# Super_IO.net
KiCad netlist of a schematic drawn in Altium Designer
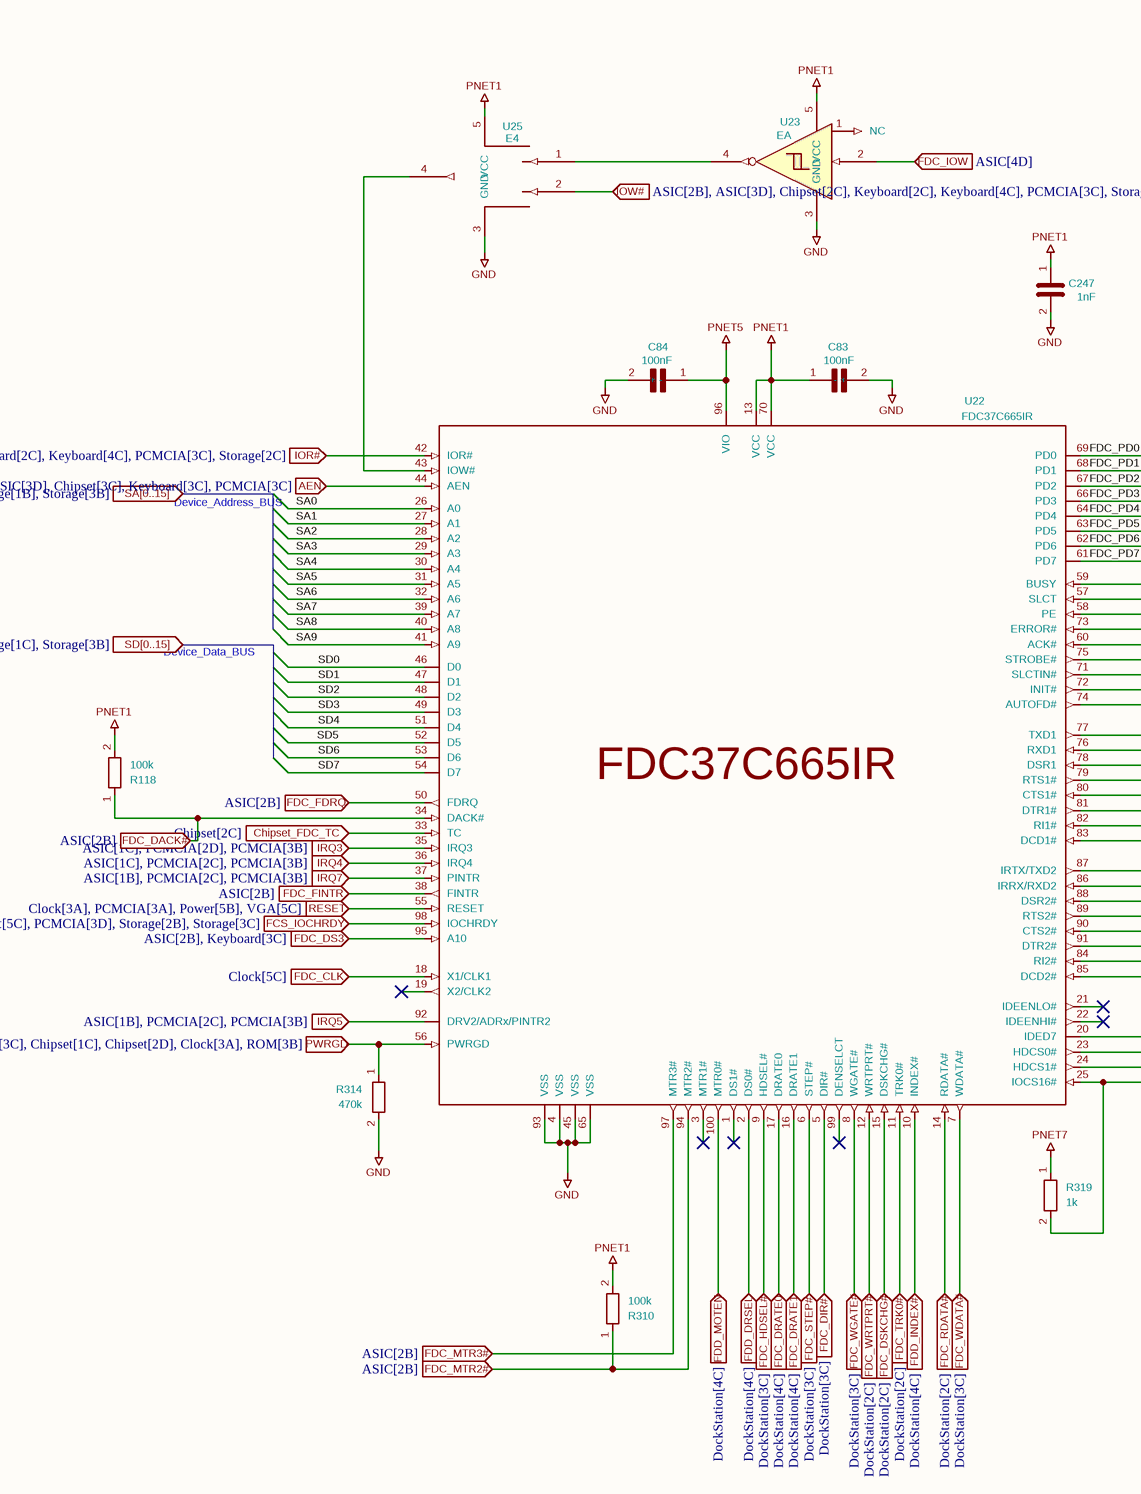
[diagram p0: Super_IO.SchDoc, left]
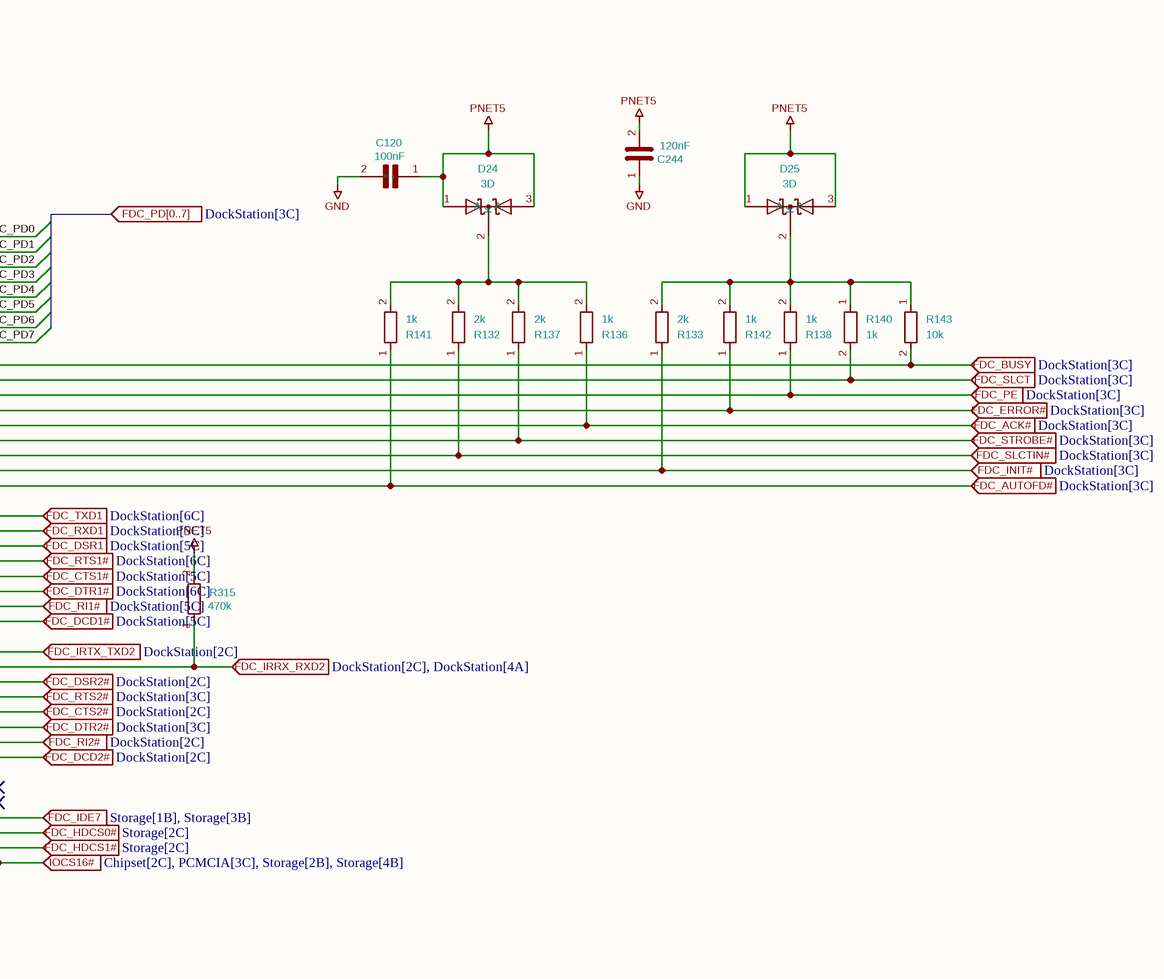
[diagram p1: Super_IO.SchDoc, right]

(export (version "E")
  (design (tool "Eeschema 10.0.6"))
  (components
    (comp (ref "C83") (value "100nF") (footprint "C_0402_1005Metric") (libsource (lib "") (part "C_1")))
    (comp (ref "C84")
      (value "100nF")
      (footprint "C_0402_1005Metric")
      (libsource (lib "PCM_Elektuur") (part "C"))
    )
    (comp (ref "C120")
      (value "100nF")
      (footprint "C_0402_1005Metric")
      (libsource (lib "PCM_Elektuur") (part "C"))
    )
    (comp (ref "C244") (value "120nF") (footprint "C_0402_1005Metric") (libsource (lib "Device") (part "C")))
    (comp (ref "C247") (value "1nF") (footprint "C_0402_1005Metric") (libsource (lib "Device") (part "C")))
    (comp (ref "D24")
      (value "3D")
      (footprint "3D")
      (libsource (lib "Device") (part "D_Schottky_Dual_CommonCathode_AKA"))
    )
    (comp (ref "D25")
      (value "3D")
      (footprint "3D")
      (libsource (lib "Device") (part "D_Schottky_Dual_CommonCathode_AKA"))
    )
    (comp (ref "R118") (value "100k") (footprint "R_0402_1005Metric") (libsource (lib "Device") (part "R")))
    (comp (ref "R132") (value "2k") (footprint "R_0402_1005Metric") (libsource (lib "Device") (part "R")))
    (comp (ref "R133") (value "2k") (footprint "R_0402_1005Metric") (libsource (lib "Device") (part "R")))
    (comp (ref "R136") (value "1k") (footprint "R_0402_1005Metric") (libsource (lib "Device") (part "R")))
    (comp (ref "R137") (value "2k") (footprint "R_0402_1005Metric") (libsource (lib "Device") (part "R")))
    (comp (ref "R138") (value "1k") (footprint "R_0402_1005Metric") (libsource (lib "Device") (part "R")))
    (comp (ref "R140") (value "1k") (footprint "R_0402_1005Metric") (libsource (lib "") (part "R_1")))
    (comp (ref "R141") (value "1k") (footprint "R_0402_1005Metric") (libsource (lib "Device") (part "R")))
    (comp (ref "R142") (value "1k") (footprint "R_0402_1005Metric") (libsource (lib "Device") (part "R")))
    (comp (ref "R143") (value "10k") (footprint "R_0402_1005Metric") (libsource (lib "") (part "R_1")))
    (comp (ref "R310") (value "100k") (footprint "R_0402_1005Metric") (libsource (lib "Device") (part "R")))
    (comp (ref "R314") (value "470k") (footprint "R_0402_1005Metric") (libsource (lib "") (part "R_2")))
    (comp (ref "R315") (value "470k") (footprint "R_0402_1005Metric") (libsource (lib "Device") (part "R")))
    (comp (ref "R319") (value "1k") (footprint "R_0402_1005Metric") (libsource (lib "") (part "R_1")))
    (comp (ref "U22") (value "FDC37C665IR") (footprint "FDC") (libsource (lib "PC110") (part "FDC37C665IR")))
    (comp (ref "U23") (value "EA") (footprint "SOT-353") (libsource (lib "74xGxx") (part "74AHC1G14")))
    (comp (ref "U25") (value "E4") (footprint "SOT-353") (libsource (lib "74xGxx") (part "74AHC1G32")))
  )
  (nets
    (net (code "15") (name "/AEN") (class "Default")
      (node (ref "U22") (pin "44") (pinfunction "AEN_44") (pintype "input"))
    )
    (net (code "16") (name "/Chipset_FDC_TC") (class "Default")
      (node (ref "U22") (pin "33") (pinfunction "TC_33") (pintype "input"))
    )
    (net (code "17") (name "/FCS_IOCHRDY") (class "Default")
      (node (ref "U22") (pin "98") (pinfunction "IOCHRDY_98") (pintype "input"))
    )
    (net (code "18") (name "/FDC_ACK#") (class "Default")
      (node (ref "R136") (pin "1") (pinfunction "1_1") (pintype "passive"))
      (node (ref "U22") (pin "60") (pinfunction "ACK#_60") (pintype "input"))
    )
    (net (code "19") (name "/FDC_AUTOFD#") (class "Default")
      (node (ref "R141") (pin "1") (pinfunction "1_1") (pintype "passive"))
      (node (ref "U22") (pin "74") (pinfunction "AUTOFD#_74") (pintype "output"))
    )
    (net (code "20") (name "/FDC_BUSY") (class "Default")
      (node (ref "R143") (pin "2") (pinfunction "2_2") (pintype "passive"))
      (node (ref "U22") (pin "59") (pinfunction "BUSY_59") (pintype "input"))
    )
    (net (code "21") (name "/FDC_CLK") (class "Default")
      (node (ref "U22") (pin "18") (pinfunction "X1/CLK1_18") (pintype "input"))
    )
    (net (code "22") (name "/FDC_CTS1#") (class "Default")
      (node (ref "U22") (pin "80") (pinfunction "CTS1#_80") (pintype "input"))
    )
    (net (code "23") (name "/FDC_CTS2#") (class "Default")
      (node (ref "U22") (pin "90") (pinfunction "CTS2#_90") (pintype "input"))
    )
    (net (code "24") (name "/FDC_DACK#") (class "Default")
      (node (ref "R118") (pin "1") (pinfunction "1_1") (pintype "passive"))
      (node (ref "U22") (pin "34") (pinfunction "DACK#_34") (pintype "input"))
    )
    (net (code "25") (name "/FDC_DCD1#") (class "Default")
      (node (ref "U22") (pin "83") (pinfunction "DCD1#_83") (pintype "input"))
    )
    (net (code "26") (name "/FDC_DCD2#") (class "Default")
      (node (ref "U22") (pin "85") (pinfunction "DCD2#_85") (pintype "input"))
    )
    (net (code "27") (name "/FDC_DIR#") (class "Default")
      (node (ref "U22") (pin "5") (pinfunction "DIR#_5") (pintype "output"))
    )
    (net (code "28") (name "/FDC_DRATE0") (class "Default")
      (node (ref "U22") (pin "17") (pinfunction "DRATE0_17") (pintype "output"))
    )
    (net (code "29") (name "/FDC_DRATE1") (class "Default")
      (node (ref "U22") (pin "16") (pinfunction "DRATE1_16") (pintype "output"))
    )
    (net (code "30") (name "/FDC_DS3") (class "Default")
      (node (ref "U22") (pin "95") (pinfunction "A10_95") (pintype "input"))
    )
    (net (code "31") (name "/FDC_DSKCHG#") (class "Default")
      (node (ref "U22") (pin "15") (pinfunction "DSKCHG#_15") (pintype "input"))
    )
    (net (code "32") (name "/FDC_DSR1") (class "Default")
      (node (ref "U22") (pin "78") (pinfunction "DSR1_78") (pintype "input"))
    )
    (net (code "33") (name "/FDC_DSR2#") (class "Default")
      (node (ref "U22") (pin "88") (pinfunction "DSR2#_88") (pintype "input"))
    )
    (net (code "34") (name "/FDC_DTR1#") (class "Default")
      (node (ref "U22") (pin "81") (pinfunction "DTR1#_81") (pintype "output"))
    )
    (net (code "35") (name "/FDC_DTR2#") (class "Default")
      (node (ref "U22") (pin "91") (pinfunction "DTR2#_91") (pintype "output"))
    )
    (net (code "36") (name "/FDC_ERROR#") (class "Default")
      (node (ref "R142") (pin "1") (pinfunction "1_1") (pintype "passive"))
      (node (ref "U22") (pin "73") (pinfunction "ERROR#_73") (pintype "input"))
    )
    (net (code "37") (name "/FDC_FDRQ") (class "Default")
      (node (ref "U22") (pin "50") (pinfunction "FDRQ_50") (pintype "output"))
    )
    (net (code "38") (name "/FDC_FINTR") (class "Default")
      (node (ref "U22") (pin "38") (pinfunction "FINTR_38") (pintype "output"))
    )
    (net (code "39") (name "/FDC_HDCS0#") (class "Default")
      (node (ref "U22") (pin "23") (pinfunction "HDCS0#_23") (pintype "output"))
    )
    (net (code "40") (name "/FDC_HDCS1#") (class "Default")
      (node (ref "U22") (pin "24") (pinfunction "HDCS1#_24") (pintype "output"))
    )
    (net (code "41") (name "/FDC_HDSEL#") (class "Default")
      (node (ref "U22") (pin "9") (pinfunction "HDSEL#_9") (pintype "output"))
    )
    (net (code "42") (name "/FDC_IDE7") (class "Default")
      (node (ref "U22") (pin "20") (pinfunction "IDED7_20") (pintype "bidirectional"))
    )
    (net (code "43") (name "/FDC_INIT#") (class "Default")
      (node (ref "R133") (pin "1") (pinfunction "1_1") (pintype "passive"))
      (node (ref "U22") (pin "72") (pinfunction "INIT#_72") (pintype "output"))
    )
    (net (code "44") (name "/FDC_IOW") (class "Default")
      (node (ref "U23") (pin "2") (pinfunction "2_2") (pintype "input"))
    )
    (net (code "45") (name "/FDC_IRRX_RXD2") (class "Default")
      (node (ref "R315") (pin "1") (pinfunction "1_1") (pintype "passive"))
      (node (ref "U22") (pin "86") (pinfunction "IRRX/RXD2_86") (pintype "input"))
    )
    (net (code "46") (name "/FDC_IRTX_TXD2") (class "Default")
      (node (ref "U22") (pin "87") (pinfunction "IRTX/TXD2_87") (pintype "output"))
    )
    (net (code "47") (name "/FDC_MTR2#") (class "Default")
      (node (ref "R310") (pin "1") (pinfunction "1_1") (pintype "passive"))
      (node (ref "U22") (pin "94") (pinfunction "MTR2#_94") (pintype "output"))
    )
    (net (code "48") (name "/FDC_MTR3#") (class "Default")
      (node (ref "U22") (pin "97") (pinfunction "MTR3#_97") (pintype "output"))
    )
    (net (code "49") (name "/FDC_PD0") (class "Default")
      (node (ref "U22") (pin "69") (pinfunction "PD0_69") (pintype "bidirectional"))
    )
    (net (code "50") (name "/FDC_PD1") (class "Default")
      (node (ref "U22") (pin "68") (pinfunction "PD1_68") (pintype "bidirectional"))
    )
    (net (code "51") (name "/FDC_PD2") (class "Default")
      (node (ref "U22") (pin "67") (pinfunction "PD2_67") (pintype "bidirectional"))
    )
    (net (code "52") (name "/FDC_PD3") (class "Default")
      (node (ref "U22") (pin "66") (pinfunction "PD3_66") (pintype "bidirectional"))
    )
    (net (code "53") (name "/FDC_PD4") (class "Default")
      (node (ref "U22") (pin "64") (pinfunction "PD4_64") (pintype "bidirectional"))
    )
    (net (code "54") (name "/FDC_PD5") (class "Default")
      (node (ref "U22") (pin "63") (pinfunction "PD5_63") (pintype "bidirectional"))
    )
    (net (code "55") (name "/FDC_PD6") (class "Default")
      (node (ref "U22") (pin "62") (pinfunction "PD6_62") (pintype "bidirectional"))
    )
    (net (code "56") (name "/FDC_PD7") (class "Default")
      (node (ref "U22") (pin "61") (pinfunction "PD7_61") (pintype "bidirectional"))
    )
    (net (code "58") (name "/FDC_PE") (class "Default")
      (node (ref "R138") (pin "1") (pinfunction "1_1") (pintype "passive"))
      (node (ref "U22") (pin "58") (pinfunction "PE_58") (pintype "input"))
    )
    (net (code "59") (name "/FDC_RDATA#") (class "Default")
      (node (ref "U22") (pin "14") (pinfunction "RDATA#_14") (pintype "input"))
    )
    (net (code "60") (name "/FDC_RI1#") (class "Default")
      (node (ref "U22") (pin "82") (pinfunction "RI1#_82") (pintype "input"))
    )
    (net (code "61") (name "/FDC_RI2#") (class "Default")
      (node (ref "U22") (pin "84") (pinfunction "RI2#_84") (pintype "input"))
    )
    (net (code "62") (name "/FDC_RTS1#") (class "Default")
      (node (ref "U22") (pin "79") (pinfunction "RTS1#_79") (pintype "output"))
    )
    (net (code "63") (name "/FDC_RTS2#") (class "Default")
      (node (ref "U22") (pin "89") (pinfunction "RTS2#_89") (pintype "output"))
    )
    (net (code "64") (name "/FDC_RXD1") (class "Default")
      (node (ref "U22") (pin "76") (pinfunction "RXD1_76") (pintype "input"))
    )
    (net (code "65") (name "/FDC_SLCT") (class "Default")
      (node (ref "R140") (pin "2") (pinfunction "2_2") (pintype "passive"))
      (node (ref "U22") (pin "57") (pinfunction "SLCT_57") (pintype "input"))
    )
    (net (code "66") (name "/FDC_SLCTIN#") (class "Default")
      (node (ref "R132") (pin "1") (pinfunction "1_1") (pintype "passive"))
      (node (ref "U22") (pin "71") (pinfunction "SLCTIN#_71") (pintype "output"))
    )
    (net (code "67") (name "/FDC_STEP#") (class "Default")
      (node (ref "U22") (pin "6") (pinfunction "STEP#_6") (pintype "output"))
    )
    (net (code "68") (name "/FDC_STROBE#") (class "Default")
      (node (ref "R137") (pin "1") (pinfunction "1_1") (pintype "passive"))
      (node (ref "U22") (pin "75") (pinfunction "STROBE#_75") (pintype "output"))
    )
    (net (code "69") (name "/FDC_TRK0#") (class "Default")
      (node (ref "U22") (pin "11") (pinfunction "TRK0#_11") (pintype "input"))
    )
    (net (code "70") (name "/FDC_TXD1") (class "Default")
      (node (ref "U22") (pin "77") (pinfunction "TXD1_77") (pintype "output"))
    )
    (net (code "71") (name "/FDC_WDATA#") (class "Default")
      (node (ref "U22") (pin "7") (pinfunction "WDATA#_7") (pintype "output"))
    )
    (net (code "72") (name "/FDC_WGATE#") (class "Default")
      (node (ref "U22") (pin "8") (pinfunction "WGATE#_8") (pintype "output"))
    )
    (net (code "73") (name "/FDC_WRTPRT#") (class "Default")
      (node (ref "U22") (pin "12") (pinfunction "WRTPRT#_12") (pintype "input"))
    )
    (net (code "74") (name "/FDD_DRSEL") (class "Default")
      (node (ref "U22") (pin "2") (pinfunction "DS0#_2") (pintype "output"))
    )
    (net (code "75") (name "/FDD_INDEX#") (class "Default")
      (node (ref "U22") (pin "10") (pinfunction "INDEX#_10") (pintype "input"))
    )
    (net (code "76") (name "/FDD_MOTEN") (class "Default")
      (node (ref "U22") (pin "100") (pinfunction "MTR0#_100") (pintype "output"))
    )
    (net (code "77") (name "/IOCS16#") (class "Default")
      (node (ref "R319") (pin "2") (pinfunction "2_2") (pintype "passive"))
      (node (ref "U22") (pin "25") (pinfunction "IOCS16#_25") (pintype "input"))
    )
    (net (code "78") (name "/IOR#") (class "Default")
      (node (ref "U22") (pin "42") (pinfunction "IOR#_42") (pintype "input"))
    )
    (net (code "79") (name "/IOW#") (class "Default")
      (node (ref "U25") (pin "2") (pinfunction "2_2") (pintype "input"))
    )
    (net (code "80") (name "/IRQ3") (class "Default")
      (node (ref "U22") (pin "35") (pinfunction "IRQ3_35") (pintype "input"))
    )
    (net (code "81") (name "/IRQ4") (class "Default")
      (node (ref "U22") (pin "36") (pinfunction "IRQ4_36") (pintype "input"))
    )
    (net (code "82") (name "/IRQ5") (class "Default")
      (node (ref "U22") (pin "92") (pinfunction "DRV2/ADRx/PINTR2_92") (pintype "bidirectional"))
    )
    (net (code "83") (name "/IRQ7") (class "Default")
      (node (ref "U22") (pin "37") (pinfunction "PINTR_37") (pintype "input"))
    )
    (net (code "84") (name "/PWRGD") (class "Default")
      (node (ref "R314") (pin "1") (pinfunction "1_1") (pintype "passive"))
      (node (ref "U22") (pin "56") (pinfunction "PWRGD_56") (pintype "input"))
    )
    (net (code "85") (name "/RESET") (class "Default")
      (node (ref "U22") (pin "55") (pinfunction "RESET_55") (pintype "input"))
    )
    (net (code "86") (name "/SA0") (class "Default")
      (node (ref "U22") (pin "26") (pinfunction "A0_26") (pintype "input"))
    )
    (net (code "87") (name "/SA1") (class "Default")
      (node (ref "U22") (pin "27") (pinfunction "A1_27") (pintype "input"))
    )
    (net (code "88") (name "/SA2") (class "Default")
      (node (ref "U22") (pin "28") (pinfunction "A2_28") (pintype "input"))
    )
    (net (code "89") (name "/SA3") (class "Default")
      (node (ref "U22") (pin "29") (pinfunction "A3_29") (pintype "input"))
    )
    (net (code "90") (name "/SA4") (class "Default")
      (node (ref "U22") (pin "30") (pinfunction "A4_30") (pintype "input"))
    )
    (net (code "91") (name "/SA5") (class "Default")
      (node (ref "U22") (pin "31") (pinfunction "A5_31") (pintype "input"))
    )
    (net (code "92") (name "/SA6") (class "Default")
      (node (ref "U22") (pin "32") (pinfunction "A6_32") (pintype "input"))
    )
    (net (code "93") (name "/SA7") (class "Default")
      (node (ref "U22") (pin "39") (pinfunction "A7_39") (pintype "input"))
    )
    (net (code "94") (name "/SA8") (class "Default")
      (node (ref "U22") (pin "40") (pinfunction "A8_40") (pintype "input"))
    )
    (net (code "95") (name "/SA9") (class "Default")
      (node (ref "U22") (pin "41") (pinfunction "A9_41") (pintype "input"))
    )
    (net (code "97") (name "/SD0") (class "Default")
      (node (ref "U22") (pin "46") (pinfunction "D0_46") (pintype "bidirectional"))
    )
    (net (code "98") (name "/SD1") (class "Default")
      (node (ref "U22") (pin "47") (pinfunction "D1_47") (pintype "bidirectional"))
    )
    (net (code "99") (name "/SD2") (class "Default")
      (node (ref "U22") (pin "48") (pinfunction "D2_48") (pintype "bidirectional"))
    )
    (net (code "100") (name "/SD3") (class "Default")
      (node (ref "U22") (pin "49") (pinfunction "D3_49") (pintype "bidirectional"))
    )
    (net (code "101") (name "/SD4") (class "Default")
      (node (ref "U22") (pin "51") (pinfunction "D4_51") (pintype "bidirectional"))
    )
    (net (code "102") (name "/SD5") (class "Default")
      (node (ref "U22") (pin "52") (pinfunction "D5_52") (pintype "bidirectional"))
    )
    (net (code "103") (name "/SD6") (class "Default")
      (node (ref "U22") (pin "53") (pinfunction "D6_53") (pintype "bidirectional"))
    )
    (net (code "104") (name "/SD7") (class "Default")
      (node (ref "U22") (pin "54") (pinfunction "D7_54") (pintype "bidirectional"))
    )
    (net (code "106") (name "GND") (class "Default")
      (node (ref "C120") (pin "2") (pinfunction "-_2") (pintype "passive"))
      (node (ref "C244") (pin "1") (pinfunction "1_1") (pintype "passive"))
      (node (ref "C247") (pin "2") (pinfunction "2_2") (pintype "passive"))
      (node (ref "C83") (pin "2") (pinfunction "-_2") (pintype "passive"))
      (node (ref "C84") (pin "2") (pinfunction "-_2") (pintype "passive"))
      (node (ref "R314") (pin "2") (pinfunction "2_2") (pintype "passive"))
      (node (ref "U22") (pin "4") (pinfunction "VSS_4") (pintype "power_in"))
      (node (ref "U22") (pin "45") (pinfunction "VSS_45") (pintype "power_in"))
      (node (ref "U22") (pin "65") (pinfunction "VSS_65") (pintype "power_in"))
      (node (ref "U22") (pin "93") (pinfunction "VSS_93") (pintype "power_in"))
      (node (ref "U23") (pin "3") (pinfunction "GND_3") (pintype "power_in"))
      (node (ref "U25") (pin "3") (pinfunction "GND_3") (pintype "power_in"))
    )
    (net (code "107") (name "Net-(D24-K)") (class "Default")
      (node (ref "D24") (pin "2") (pinfunction "K_2") (pintype "passive"))
      (node (ref "R132") (pin "2") (pinfunction "2_2") (pintype "passive"))
      (node (ref "R136") (pin "2") (pinfunction "2_2") (pintype "passive"))
      (node (ref "R137") (pin "2") (pinfunction "2_2") (pintype "passive"))
      (node (ref "R141") (pin "2") (pinfunction "2_2") (pintype "passive"))
    )
    (net (code "108") (name "Net-(D25-K)") (class "Default")
      (node (ref "D25") (pin "2") (pinfunction "K_2") (pintype "passive"))
      (node (ref "R133") (pin "2") (pinfunction "2_2") (pintype "passive"))
      (node (ref "R138") (pin "2") (pinfunction "2_2") (pintype "passive"))
      (node (ref "R140") (pin "1") (pinfunction "1_1") (pintype "passive"))
      (node (ref "R142") (pin "2") (pinfunction "2_2") (pintype "passive"))
      (node (ref "R143") (pin "1") (pinfunction "1_1") (pintype "passive"))
    )
    (net (code "109") (name "Net-(U22-IOW#)") (class "Default")
      (node (ref "U22") (pin "43") (pinfunction "IOW#_43") (pintype "input"))
      (node (ref "U25") (pin "4") (pinfunction "4_4") (pintype "output"))
    )
    (net (code "110") (name "Net-(U23-Pad4)") (class "Default")
      (node (ref "U23") (pin "4") (pinfunction "4_4") (pintype "output"))
      (node (ref "U25") (pin "1") (pinfunction "1_1") (pintype "input"))
    )
    (net (code "111") (name "PNET1") (class "Default")
      (node (ref "C247") (pin "1") (pinfunction "1_1") (pintype "passive"))
      (node (ref "C83") (pin "1") (pinfunction "+_1") (pintype "passive"))
      (node (ref "R118") (pin "2") (pinfunction "2_2") (pintype "passive"))
      (node (ref "R310") (pin "2") (pinfunction "2_2") (pintype "passive"))
      (node (ref "U22") (pin "13") (pinfunction "VCC_13") (pintype "power_in"))
      (node (ref "U22") (pin "70") (pinfunction "VCC_70") (pintype "power_in"))
      (node (ref "U23") (pin "5") (pinfunction "VCC_5") (pintype "power_in"))
      (node (ref "U25") (pin "5") (pinfunction "VCC_5") (pintype "power_in"))
    )
    (net (code "112") (name "PNET5") (class "Default")
      (node (ref "C120") (pin "1") (pinfunction "+_1") (pintype "passive"))
      (node (ref "C244") (pin "2") (pinfunction "2_2") (pintype "passive"))
      (node (ref "C84") (pin "1") (pinfunction "+_1") (pintype "passive"))
      (node (ref "D24") (pin "1") (pinfunction "A_1") (pintype "passive"))
      (node (ref "D24") (pin "3") (pinfunction "A_3") (pintype "passive"))
      (node (ref "D25") (pin "1") (pinfunction "A_1") (pintype "passive"))
      (node (ref "D25") (pin "3") (pinfunction "A_3") (pintype "passive"))
      (node (ref "R315") (pin "2") (pinfunction "2_2") (pintype "passive"))
      (node (ref "U22") (pin "96") (pinfunction "VIO_96") (pintype "power_in"))
    )
    (net (code "113") (name "PNET7") (class "Default")
      (node (ref "R319") (pin "1") (pinfunction "1_1") (pintype "passive"))
    )
    (net (code "114") (name "unconnected-(U22-DENSELCT-Pad99)") (class "Default")
      (node (ref "U22") (pin "99") (pinfunction "DENSELCT_99") (pintype "output+no_connect"))
    )
    (net (code "115") (name "unconnected-(U22-DS1#-Pad1)") (class "Default")
      (node (ref "U22") (pin "1") (pinfunction "DS1#_1") (pintype "output+no_connect"))
    )
    (net (code "116") (name "unconnected-(U22-IDEENHI#-Pad22)") (class "Default")
      (node (ref "U22") (pin "22") (pinfunction "IDEENHI#_22") (pintype "output+no_connect"))
    )
    (net (code "117") (name "unconnected-(U22-IDEENLO#-Pad21)") (class "Default")
      (node (ref "U22") (pin "21") (pinfunction "IDEENLO#_21") (pintype "output+no_connect"))
    )
    (net (code "118") (name "unconnected-(U22-MTR1#-Pad3)") (class "Default")
      (node (ref "U22") (pin "3") (pinfunction "MTR1#_3") (pintype "output+no_connect"))
    )
    (net (code "119") (name "unconnected-(U22-X2{slash}CLK2-Pad19)") (class "Default")
      (node (ref "U22") (pin "19") (pinfunction "X2/CLK2_19") (pintype "output+no_connect"))
    )
    (net (code "120") (name "unconnected-(U23-NC-Pad1)") (class "Default")
      (node (ref "U23") (pin "1") (pinfunction "NC_1") (pintype "input"))
    )
  )
)
